# GPS_radiologger_v20_CAM_M8Q.net
KiCad netlist of a schematic drawn in EAGLE
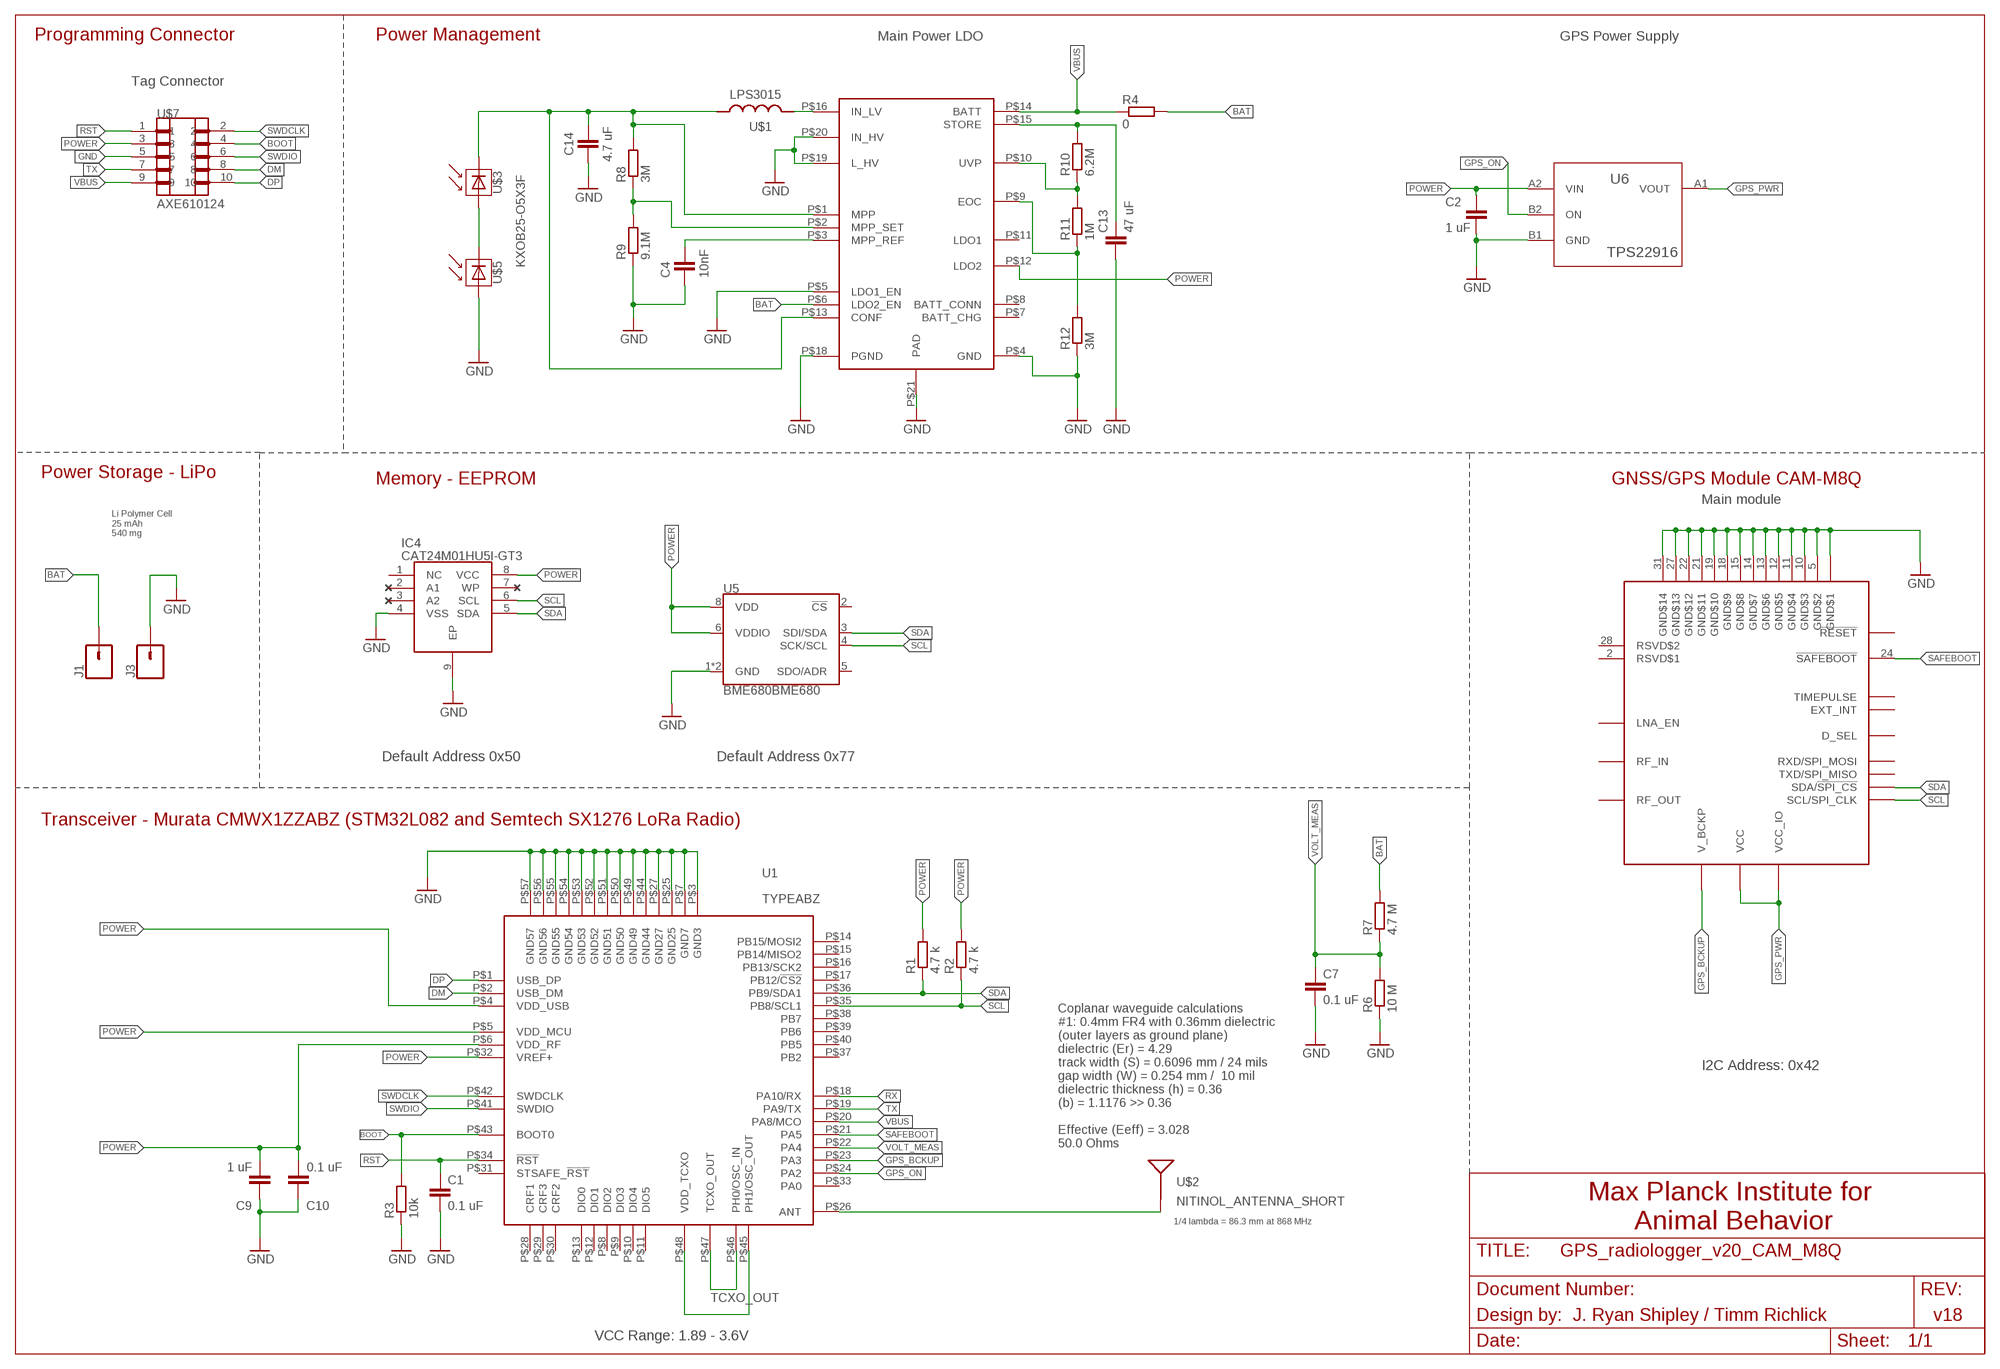
[diagram p0: schematic, sheet 1]

(export (version "E")
  (design (tool "Eeschema 10.0.6"))
  (components
    (comp (ref "C1")
      (value "0.1 uF")
      (footprint "eagle-import:C0201")
      (libsource (lib "eagle-import") (part "C-EUC0201"))
    )
    (comp (ref "C2")
      (value "1 uF")
      (footprint "eagle-import:C0201")
      (libsource (lib "eagle-import") (part "C-EUC0201"))
    )
    (comp (ref "C4")
      (value "10nF")
      (footprint "eagle-import:C0201")
      (libsource (lib "eagle-import") (part "C-EUC0201"))
    )
    (comp (ref "C7")
      (value "0.1 uF")
      (footprint "eagle-import:C0201")
      (libsource (lib "eagle-import") (part "C-EUC0201"))
    )
    (comp (ref "C9")
      (value "1 uF")
      (footprint "eagle-import:C0201")
      (libsource (lib "eagle-import") (part "C-EUC0201"))
    )
    (comp (ref "C10")
      (value "0.1 uF")
      (footprint "eagle-import:C0201")
      (libsource (lib "eagle-import") (part "C-EUC0201"))
    )
    (comp (ref "C13")
      (value "47 uF")
      (footprint "eagle-import:C0805K")
      (libsource (lib "eagle-import") (part "C-EUC0805K"))
    )
    (comp (ref "C14")
      (value "4.7 uF")
      (footprint "eagle-import:C0201")
      (libsource (lib "eagle-import") (part "C-EUC0201"))
    )
    (comp (ref "IC4")
      (value "CAT24M01HU5I-GT3")
      (footprint "eagle-import:SON50P300X200X55-9N")
      (fields
        (field (name "MOUSER_PART_NUMBER") "863-CAT24M01HU5I-GT3")
        (field (name "RS_PART_NUMBER") "7814831P")
      )
      (libsource (lib "eagle-import") (part "CAT24M01HU5I-GT3"))
    )
    (comp (ref "J1")
      (value "CONN_01PTH_NO_SILK_YES_STOP")
      (footprint "eagle-import:1X01_NO_SILK")
      (libsource (lib "eagle-import") (part "CONN_01PTH_NO_SILK_YES_STOP"))
    )
    (comp (ref "J3")
      (value "CONN_01PTH_NO_SILK_YES_STOP")
      (footprint "eagle-import:1X01_NO_SILK")
      (libsource (lib "eagle-import") (part "CONN_01PTH_NO_SILK_YES_STOP"))
    )
    (comp (ref "R1")
      (value "4.7 k")
      (footprint "eagle-import:R0201")
      (libsource (lib "eagle-import") (part "R-EU_R0201"))
    )
    (comp (ref "R2")
      (value "4.7 k")
      (footprint "eagle-import:R0201")
      (libsource (lib "eagle-import") (part "R-EU_R0201"))
    )
    (comp (ref "R3")
      (value "10k")
      (footprint "eagle-import:R0201")
      (libsource (lib "eagle-import") (part "R-EU_R0201"))
    )
    (comp (ref "R4")
      (value "0")
      (footprint "eagle-import:R0201")
      (libsource (lib "eagle-import") (part "R-EU_R0201"))
    )
    (comp (ref "R6")
      (value "10 M")
      (footprint "eagle-import:R0201")
      (libsource (lib "eagle-import") (part "R-EU_R0201"))
    )
    (comp (ref "R7")
      (value "4.7 M")
      (footprint "eagle-import:R0201")
      (libsource (lib "eagle-import") (part "R-EU_R0201"))
    )
    (comp (ref "R8")
      (value "3M")
      (footprint "eagle-import:R0201")
      (libsource (lib "eagle-import") (part "R-EU_R0201"))
    )
    (comp (ref "R9")
      (value "9.1M")
      (footprint "eagle-import:R0201")
      (libsource (lib "eagle-import") (part "R-EU_R0201"))
    )
    (comp (ref "R10")
      (value "6.2M")
      (footprint "eagle-import:R0201")
      (libsource (lib "eagle-import") (part "R-EU_R0201"))
    )
    (comp (ref "R11")
      (value "1M")
      (footprint "eagle-import:R0201")
      (libsource (lib "eagle-import") (part "R-EU_R0201"))
    )
    (comp (ref "R12")
      (value "3M")
      (footprint "eagle-import:R0201")
      (libsource (lib "eagle-import") (part "R-EU_R0201"))
    )
    (comp (ref "U$1")
      (value "LPS3015")
      (footprint "eagle-import:LPS_3015")
      (libsource (lib "eagle-import") (part "LPS3015"))
    )
    (comp (ref "U$2")
      (value "NITINOL_ANTENNA_SHORT")
      (footprint "eagle-import:ICARUS_NITINOL_ANTENNA_SHORT")
      (libsource (lib "eagle-import") (part "NITINOL_ANTENNA_SHORT"))
    )
    (comp (ref "U$3")
      (value "KXOB25-O5X3F")
      (footprint "eagle-import:KXOB25-05X3F")
      (libsource (lib "eagle-import") (part "KXOB25-O5X3F"))
    )
    (comp (ref "U$4")
      (value "CAM-M8")
      (footprint "eagle-import:CAM-M8")
      (libsource (lib "eagle-import") (part "CAM-M8"))
    )
    (comp (ref "U$5")
      (value "KXOB25-O5X3F")
      (footprint "eagle-import:KXOB25-05X3F")
      (libsource (lib "eagle-import") (part "KXOB25-O5X3F"))
    )
    (comp (ref "U$7")
      (value "AXE610124")
      (footprint "eagle-import:AXE610124")
      (libsource (lib "eagle-import") (part "AXE610124"))
    )
    (comp (ref "U1")
      (value "TYPEABZ")
      (footprint "eagle-import:TYPEABZ")
      (libsource (lib "eagle-import") (part "TYPEABZ"))
    )
    (comp (ref "U4")
      (value "SPV1050")
      (footprint "eagle-import:SPV1050")
      (libsource (lib "eagle-import") (part "SPV1050"))
    )
    (comp (ref "U5")
      (value "BME680BME680")
      (footprint "eagle-import:LGA3.0X3.0")
      (libsource (lib "eagle-import") (part "BME680BME680"))
    )
    (comp (ref "U6")
      (value "TPS22916")
      (footprint "eagle-import:TPS22916")
      (fields (field (name "MF") "Texas Instruments") (field (name "MP") "LP5900TL-3.0"))
      (libsource (lib "eagle-import") (part "TPS22916"))
    )
  )
  (nets
    (net (code "1") (name "/TCXO_OUT") (class "Default")
      (node (ref "U1") (pin "P$46") (pinfunction "PH0/OSC_IN_P$46") (pintype "bidirectional"))
      (node (ref "U1") (pin "P$47") (pinfunction "TCXO_OUT_P$47") (pintype "bidirectional"))
    )
    (net (code "2") (name "BAT") (class "Default")
      (node (ref "J1") (pin "1") (pinfunction "1_1") (pintype "passive"))
      (node (ref "R4") (pin "2") (pinfunction "2_2") (pintype "passive"))
      (node (ref "R7") (pin "2") (pinfunction "2_2") (pintype "passive"))
      (node (ref "U4") (pin "P$6") (pinfunction "LDO2_EN_P$6") (pintype "input"))
    )
    (net (code "3") (name "BOOT") (class "Default")
      (node (ref "R3") (pin "2") (pinfunction "2_2") (pintype "passive"))
      (node (ref "U$7") (pin "4") (pinfunction "4_4") (pintype "passive"))
      (node (ref "U1") (pin "P$43") (pinfunction "BOOT0_P$43") (pintype "bidirectional"))
    )
    (net (code "4") (name "DM") (class "Default")
      (node (ref "U$7") (pin "8") (pinfunction "8_8") (pintype "passive"))
      (node (ref "U1") (pin "P$2") (pinfunction "USB_DM_P$2") (pintype "bidirectional"))
    )
    (net (code "5") (name "DP") (class "Default")
      (node (ref "U$7") (pin "10") (pinfunction "10_10") (pintype "passive"))
      (node (ref "U1") (pin "P$1") (pinfunction "USB_DP_P$1") (pintype "bidirectional"))
    )
    (net (code "6") (name "GND") (class "Default")
      (node (ref "C1") (pin "2") (pinfunction "2_2") (pintype "passive"))
      (node (ref "C10") (pin "1") (pinfunction "1_1") (pintype "passive"))
      (node (ref "C13") (pin "2") (pinfunction "2_2") (pintype "passive"))
      (node (ref "C14") (pin "2") (pinfunction "2_2") (pintype "passive"))
      (node (ref "C2") (pin "2") (pinfunction "2_2") (pintype "passive"))
      (node (ref "C4") (pin "2") (pinfunction "2_2") (pintype "passive"))
      (node (ref "C7") (pin "2") (pinfunction "2_2") (pintype "passive"))
      (node (ref "C9") (pin "1") (pinfunction "1_1") (pintype "passive"))
      (node (ref "IC4") (pin "4") (pinfunction "VSS_4") (pintype "power_in"))
      (node (ref "IC4") (pin "9") (pinfunction "EP_9") (pintype "bidirectional"))
      (node (ref "J3") (pin "1") (pinfunction "1_1") (pintype "passive"))
      (node (ref "R12") (pin "1") (pinfunction "1_1") (pintype "passive"))
      (node (ref "R3") (pin "1") (pinfunction "1_1") (pintype "passive"))
      (node (ref "R6") (pin "1") (pinfunction "1_1") (pintype "passive"))
      (node (ref "R9") (pin "1") (pinfunction "1_1") (pintype "passive"))
      (node (ref "U$4") (pin "10") (pinfunction "GND$3_10") (pintype "power_in"))
      (node (ref "U$4") (pin "11") (pinfunction "GND$4_11") (pintype "power_in"))
      (node (ref "U$4") (pin "12") (pinfunction "GND$5_12") (pintype "power_in"))
      (node (ref "U$4") (pin "13") (pinfunction "GND$6_13") (pintype "power_in"))
      (node (ref "U$4") (pin "14") (pinfunction "GND$7_14") (pintype "power_in"))
      (node (ref "U$4") (pin "15") (pinfunction "GND$8_15") (pintype "power_in"))
      (node (ref "U$4") (pin "18") (pinfunction "GND$9_18") (pintype "power_in"))
      (node (ref "U$4") (pin "19") (pinfunction "GND$10_19") (pintype "power_in"))
      (node (ref "U$4") (pin "21") (pinfunction "GND$11_21") (pintype "power_in"))
      (node (ref "U$4") (pin "22") (pinfunction "GND$12_22") (pintype "power_in"))
      (node (ref "U$4") (pin "27") (pinfunction "GND$13_27") (pintype "power_in"))
      (node (ref "U$4") (pin "31") (pinfunction "GND$14_31") (pintype "power_in"))
      (node (ref "U$4") (pin "4") (pinfunction "GND$1_4") (pintype "power_in"))
      (node (ref "U$4") (pin "5") (pinfunction "GND$2_5") (pintype "power_in"))
      (node (ref "U$5") (pin "P$2") (pinfunction "MINUS_P$2") (pintype "passive"))
      (node (ref "U$7") (pin "5") (pinfunction "5_5") (pintype "passive"))
      (node (ref "U1") (pin "P$25") (pinfunction "GND25_P$25") (pintype "power_in"))
      (node (ref "U1") (pin "P$27") (pinfunction "GND27_P$27") (pintype "power_in"))
      (node (ref "U1") (pin "P$3") (pinfunction "GND3_P$3") (pintype "power_in"))
      (node (ref "U1") (pin "P$44") (pinfunction "GND44_P$44") (pintype "power_in"))
      (node (ref "U1") (pin "P$49") (pinfunction "GND49_P$49") (pintype "power_in"))
      (node (ref "U1") (pin "P$50") (pinfunction "GND50_P$50") (pintype "power_in"))
      (node (ref "U1") (pin "P$51") (pinfunction "GND51_P$51") (pintype "power_in"))
      (node (ref "U1") (pin "P$52") (pinfunction "GND52_P$52") (pintype "power_in"))
      (node (ref "U1") (pin "P$53") (pinfunction "GND53_P$53") (pintype "power_in"))
      (node (ref "U1") (pin "P$54") (pinfunction "GND54_P$54") (pintype "power_in"))
      (node (ref "U1") (pin "P$55") (pinfunction "GND55_P$55") (pintype "power_in"))
      (node (ref "U1") (pin "P$56") (pinfunction "GND56_P$56") (pintype "power_in"))
      (node (ref "U1") (pin "P$57") (pinfunction "GND57_P$57") (pintype "power_in"))
      (node (ref "U1") (pin "P$7") (pinfunction "GND7_P$7") (pintype "power_in"))
      (node (ref "U4") (pin "P$18") (pinfunction "PGND_P$18") (pintype "power_in"))
      (node (ref "U4") (pin "P$19") (pinfunction "L_HV_P$19") (pintype "power_in"))
      (node (ref "U4") (pin "P$20") (pinfunction "IN_HV_P$20") (pintype "power_in"))
      (node (ref "U4") (pin "P$21") (pinfunction "PAD_P$21") (pintype "power_in"))
      (node (ref "U4") (pin "P$4") (pinfunction "GND_P$4") (pintype "power_in"))
      (node (ref "U4") (pin "P$5") (pinfunction "LDO1_EN_P$5") (pintype "input"))
      (node (ref "U5") (pin "1") (pinfunction "GND_1") (pintype "bidirectional"))
      (node (ref "U5") (pin "7") (pinfunction "GND_7") (pintype "bidirectional"))
      (node (ref "U6") (pin "B1") (pinfunction "GND_B1") (pintype "passive"))
    )
    (net (code "7") (name "GPS_BCKUP") (class "Default")
      (node (ref "U$4") (pin "8") (pinfunction "V_BCKP_8") (pintype "power_in"))
      (node (ref "U1") (pin "P$23") (pinfunction "PA3_P$23") (pintype "bidirectional"))
    )
    (net (code "8") (name "GPS_ON") (class "Default")
      (node (ref "U1") (pin "P$24") (pinfunction "PA2_P$24") (pintype "bidirectional"))
      (node (ref "U6") (pin "B2") (pinfunction "ON_B2") (pintype "input"))
    )
    (net (code "9") (name "GPS_PWR") (class "Default")
      (node (ref "U$4") (pin "1") (pinfunction "VCC_IO_1") (pintype "power_in"))
      (node (ref "U$4") (pin "9") (pinfunction "VCC_9") (pintype "power_in"))
      (node (ref "U6") (pin "A1") (pinfunction "VOUT_A1") (pintype "output"))
    )
    (net (code "10") (name "Net-(U$1-1)") (class "Default")
      (node (ref "C14") (pin "1") (pinfunction "1_1") (pintype "passive"))
      (node (ref "R8") (pin "2") (pinfunction "2_2") (pintype "passive"))
      (node (ref "U$1") (pin "P$1") (pinfunction "1_P$1") (pintype "passive"))
      (node (ref "U$3") (pin "P$1") (pinfunction "PLUS_P$1") (pintype "passive"))
      (node (ref "U4") (pin "P$1") (pinfunction "MPP_P$1") (pintype "input"))
      (node (ref "U4") (pin "P$13") (pinfunction "CONF_P$13") (pintype "input"))
    )
    (net (code "11") (name "Net-(U$1-2)") (class "Default")
      (node (ref "U$1") (pin "P$2") (pinfunction "2_P$2") (pintype "passive"))
      (node (ref "U4") (pin "P$16") (pinfunction "IN_LV_P$16") (pintype "power_in"))
    )
    (net (code "12") (name "Net-(U$3-MINUS)") (class "Default")
      (node (ref "U$3") (pin "P$2") (pinfunction "MINUS_P$2") (pintype "passive"))
      (node (ref "U$5") (pin "P$1") (pinfunction "PLUS_P$1") (pintype "passive"))
    )
    (net (code "13") (name "Net-(U1-ANT)") (class "Default")
      (node (ref "U$2") (pin "1") (pinfunction "SIGNAL_1") (pintype "bidirectional"))
      (node (ref "U$2") (pin "2") (pinfunction "SIGNAL_2") (pintype "bidirectional"))
      (node (ref "U$2") (pin "3") (pinfunction "SIGNAL_3") (pintype "bidirectional"))
      (node (ref "U1") (pin "P$26") (pinfunction "ANT_P$26") (pintype "bidirectional"))
    )
    (net (code "14") (name "Net-(U1-PH1{slash}OSC_OUT)") (class "Default")
      (node (ref "U1") (pin "P$45") (pinfunction "PH1/OSC_OUT_P$45") (pintype "bidirectional"))
      (node (ref "U1") (pin "P$48") (pinfunction "VDD_TCXO_P$48") (pintype "power_in"))
    )
    (net (code "15") (name "Net-(U4-EOC)") (class "Default")
      (node (ref "R11") (pin "1") (pinfunction "1_1") (pintype "passive"))
      (node (ref "R12") (pin "2") (pinfunction "2_2") (pintype "passive"))
      (node (ref "U4") (pin "P$9") (pinfunction "EOC_P$9") (pintype "input"))
    )
    (net (code "16") (name "Net-(U4-MPP_REF)") (class "Default")
      (node (ref "C4") (pin "1") (pinfunction "1_1") (pintype "passive"))
      (node (ref "U4") (pin "P$3") (pinfunction "MPP_REF_P$3") (pintype "input"))
    )
    (net (code "17") (name "Net-(U4-MPP_SET)") (class "Default")
      (node (ref "R8") (pin "1") (pinfunction "1_1") (pintype "passive"))
      (node (ref "R9") (pin "2") (pinfunction "2_2") (pintype "passive"))
      (node (ref "U4") (pin "P$2") (pinfunction "MPP_SET_P$2") (pintype "input"))
    )
    (net (code "18") (name "Net-(U4-STORE)") (class "Default")
      (node (ref "C13") (pin "1") (pinfunction "1_1") (pintype "passive"))
      (node (ref "R10") (pin "2") (pinfunction "2_2") (pintype "passive"))
      (node (ref "U4") (pin "P$15") (pinfunction "STORE_P$15") (pintype "bidirectional"))
    )
    (net (code "19") (name "Net-(U4-UVP)") (class "Default")
      (node (ref "R10") (pin "1") (pinfunction "1_1") (pintype "passive"))
      (node (ref "R11") (pin "2") (pinfunction "2_2") (pintype "passive"))
      (node (ref "U4") (pin "P$10") (pinfunction "UVP_P$10") (pintype "input"))
    )
    (net (code "20") (name "POWER") (class "Default")
      (node (ref "C10") (pin "2") (pinfunction "2_2") (pintype "passive"))
      (node (ref "C2") (pin "1") (pinfunction "1_1") (pintype "passive"))
      (node (ref "C9") (pin "2") (pinfunction "2_2") (pintype "passive"))
      (node (ref "IC4") (pin "8") (pinfunction "VCC_8") (pintype "power_in"))
      (node (ref "R1") (pin "2") (pinfunction "2_2") (pintype "passive"))
      (node (ref "R2") (pin "2") (pinfunction "2_2") (pintype "passive"))
      (node (ref "U$7") (pin "3") (pinfunction "3_3") (pintype "passive"))
      (node (ref "U1") (pin "P$32") (pinfunction "VREF+_P$32") (pintype "power_in"))
      (node (ref "U1") (pin "P$4") (pinfunction "VDD_USB_P$4") (pintype "power_in"))
      (node (ref "U1") (pin "P$5") (pinfunction "VDD_MCU_P$5") (pintype "power_in"))
      (node (ref "U1") (pin "P$6") (pinfunction "VDD_RF_P$6") (pintype "power_in"))
      (node (ref "U4") (pin "P$12") (pinfunction "LDO2_P$12") (pintype "output"))
      (node (ref "U5") (pin "6") (pinfunction "VDDIO_6") (pintype "bidirectional"))
      (node (ref "U5") (pin "8") (pinfunction "VDD_8") (pintype "bidirectional"))
      (node (ref "U6") (pin "A2") (pinfunction "VIN_A2") (pintype "power_in"))
    )
    (net (code "21") (name "RST") (class "Default")
      (node (ref "C1") (pin "1") (pinfunction "1_1") (pintype "passive"))
      (node (ref "U$7") (pin "1") (pinfunction "1_1") (pintype "passive"))
      (node (ref "U1") (pin "P$34") (pinfunction "~{RST}_P$34") (pintype "bidirectional"))
    )
    (net (code "22") (name "RX") (class "Default")
      (node (ref "U1") (pin "P$18") (pinfunction "PA10/RX_P$18") (pintype "bidirectional"))
    )
    (net (code "23") (name "SAFEBOOT") (class "Default")
      (node (ref "U$4") (pin "24") (pinfunction "~{SAFEBOOT}_24") (pintype "input"))
      (node (ref "U1") (pin "P$21") (pinfunction "PA5_P$21") (pintype "bidirectional"))
    )
    (net (code "24") (name "SCL") (class "Default")
      (node (ref "IC4") (pin "6") (pinfunction "SCL_6") (pintype "bidirectional"))
      (node (ref "R2") (pin "1") (pinfunction "1_1") (pintype "passive"))
      (node (ref "U$4") (pin "6") (pinfunction "SCL/SPI_CLK_6") (pintype "input"))
      (node (ref "U1") (pin "P$35") (pinfunction "PB8/SCL1_P$35") (pintype "bidirectional"))
      (node (ref "U5") (pin "4") (pinfunction "SCK/SCL_4") (pintype "bidirectional"))
    )
    (net (code "25") (name "SDA") (class "Default")
      (node (ref "IC4") (pin "5") (pinfunction "SDA_5") (pintype "bidirectional"))
      (node (ref "R1") (pin "1") (pinfunction "1_1") (pintype "passive"))
      (node (ref "U$4") (pin "3") (pinfunction "SDA/~{SPI_CS}_3") (pintype "bidirectional"))
      (node (ref "U1") (pin "P$36") (pinfunction "PB9/SDA1_P$36") (pintype "bidirectional"))
      (node (ref "U5") (pin "3") (pinfunction "SDI/SDA_3") (pintype "bidirectional"))
    )
    (net (code "26") (name "SWDCLK") (class "Default")
      (node (ref "U$7") (pin "2") (pinfunction "2_2") (pintype "passive"))
      (node (ref "U1") (pin "P$42") (pinfunction "SWDCLK_P$42") (pintype "bidirectional"))
    )
    (net (code "27") (name "SWDIO") (class "Default")
      (node (ref "U$7") (pin "6") (pinfunction "6_6") (pintype "passive"))
      (node (ref "U1") (pin "P$41") (pinfunction "SWDIO_P$41") (pintype "bidirectional"))
    )
    (net (code "28") (name "TX") (class "Default")
      (node (ref "U$7") (pin "7") (pinfunction "7_7") (pintype "passive"))
      (node (ref "U1") (pin "P$19") (pinfunction "PA9/TX_P$19") (pintype "bidirectional"))
    )
    (net (code "29") (name "VBUS") (class "Default")
      (node (ref "R4") (pin "1") (pinfunction "1_1") (pintype "passive"))
      (node (ref "U$7") (pin "9") (pinfunction "9_9") (pintype "passive"))
      (node (ref "U1") (pin "P$20") (pinfunction "PA8/MCO_P$20") (pintype "bidirectional"))
      (node (ref "U4") (pin "P$14") (pinfunction "BATT_P$14") (pintype "bidirectional"))
    )
    (net (code "30") (name "VOLT_MEAS") (class "Default")
      (node (ref "C7") (pin "1") (pinfunction "1_1") (pintype "passive"))
      (node (ref "R6") (pin "2") (pinfunction "2_2") (pintype "passive"))
      (node (ref "R7") (pin "1") (pinfunction "1_1") (pintype "passive"))
      (node (ref "U1") (pin "P$22") (pinfunction "PA4_P$22") (pintype "bidirectional"))
    )
    (net (code "31") (name "unconnected-(IC4-A1-Pad2)") (class "Default")
      (node (ref "IC4") (pin "2") (pinfunction "A1_2") (pintype "bidirectional"))
    )
    (net (code "32") (name "unconnected-(IC4-A2-Pad3)") (class "Default")
      (node (ref "IC4") (pin "3") (pinfunction "A2_3") (pintype "bidirectional"))
    )
    (net (code "33") (name "unconnected-(IC4-NC-Pad1)") (class "Default")
      (node (ref "IC4") (pin "1") (pinfunction "NC_1") (pintype "no_connect"))
    )
    (net (code "34") (name "unconnected-(IC4-WP-Pad7)") (class "Default")
      (node (ref "IC4") (pin "7") (pinfunction "WP_7") (pintype "bidirectional"))
    )
    (net (code "35") (name "unconnected-(U$4-D_SEL-Pad20)") (class "Default")
      (node (ref "U$4") (pin "20") (pinfunction "D_SEL_20") (pintype "input"))
    )
    (net (code "36") (name "unconnected-(U$4-EXT_INT-Pad7)") (class "Default")
      (node (ref "U$4") (pin "7") (pinfunction "EXT_INT_7") (pintype "bidirectional"))
    )
    (net (code "37") (name "unconnected-(U$4-LNA_EN-Pad30)") (class "Default")
      (node (ref "U$4") (pin "30") (pinfunction "LNA_EN_30") (pintype "output"))
    )
    (net (code "38") (name "unconnected-(U$4-RF_IN-Pad17)") (class "Default")
      (node (ref "U$4") (pin "17") (pinfunction "RF_IN_17") (pintype "input"))
    )
    (net (code "39") (name "unconnected-(U$4-RF_OUT-Pad16)") (class "Default")
      (node (ref "U$4") (pin "16") (pinfunction "RF_OUT_16") (pintype "output"))
    )
    (net (code "40") (name "unconnected-(U$4-RSVD$1-Pad2)") (class "Default")
      (node (ref "U$4") (pin "2") (pinfunction "RSVD$1_2") (pintype "no_connect"))
    )
    (net (code "41") (name "unconnected-(U$4-RSVD$2-Pad28)") (class "Default")
      (node (ref "U$4") (pin "28") (pinfunction "RSVD$2_28") (pintype "no_connect"))
    )
    (net (code "42") (name "unconnected-(U$4-RXD{slash}SPI_MOSI-Pad26)") (class "Default")
      (node (ref "U$4") (pin "26") (pinfunction "RXD/SPI_MOSI_26") (pintype "input"))
    )
    (net (code "43") (name "unconnected-(U$4-TIMEPULSE-Pad29)") (class "Default")
      (node (ref "U$4") (pin "29") (pinfunction "TIMEPULSE_29") (pintype "output"))
    )
    (net (code "44") (name "unconnected-(U$4-TXD{slash}SPI_MISO-Pad25)") (class "Default")
      (node (ref "U$4") (pin "25") (pinfunction "TXD/SPI_MISO_25") (pintype "output"))
    )
    (net (code "45") (name "unconnected-(U$4-~{RESET}-Pad23)") (class "Default")
      (node (ref "U$4") (pin "23") (pinfunction "~{RESET}_23") (pintype "input"))
    )
    (net (code "46") (name "unconnected-(U1-CRF1-PadP$28)") (class "Default")
      (node (ref "U1") (pin "P$28") (pinfunction "CRF1_P$28") (pintype "no_connect"))
    )
    (net (code "47") (name "unconnected-(U1-CRF2-PadP$30)") (class "Default")
      (node (ref "U1") (pin "P$30") (pinfunction "CRF2_P$30") (pintype "no_connect"))
    )
    (net (code "48") (name "unconnected-(U1-CRF3-PadP$29)") (class "Default")
      (node (ref "U1") (pin "P$29") (pinfunction "CRF3_P$29") (pintype "no_connect"))
    )
    (net (code "49") (name "unconnected-(U1-DIO0-PadP$13)") (class "Default")
      (node (ref "U1") (pin "P$13") (pinfunction "DIO0_P$13") (pintype "no_connect"))
    )
    (net (code "50") (name "unconnected-(U1-DIO1-PadP$12)") (class "Default")
      (node (ref "U1") (pin "P$12") (pinfunction "DIO1_P$12") (pintype "no_connect"))
    )
    (net (code "51") (name "unconnected-(U1-DIO2-PadP$8)") (class "Default")
      (node (ref "U1") (pin "P$8") (pinfunction "DIO2_P$8") (pintype "no_connect"))
    )
    (net (code "52") (name "unconnected-(U1-DIO3-PadP$9)") (class "Default")
      (node (ref "U1") (pin "P$9") (pinfunction "DIO3_P$9") (pintype "no_connect"))
    )
    (net (code "53") (name "unconnected-(U1-DIO4-PadP$10)") (class "Default")
      (node (ref "U1") (pin "P$10") (pinfunction "DIO4_P$10") (pintype "bidirectional"))
    )
    (net (code "54") (name "unconnected-(U1-DIO5-PadP$11)") (class "Default")
      (node (ref "U1") (pin "P$11") (pinfunction "DIO5_P$11") (pintype "bidirectional"))
    )
    (net (code "55") (name "unconnected-(U1-PA0-PadP$33)") (class "Default")
      (node (ref "U1") (pin "P$33") (pinfunction "PA0_P$33") (pintype "bidirectional"))
    )
    (net (code "56") (name "unconnected-(U1-PB2-PadP$37)") (class "Default")
      (node (ref "U1") (pin "P$37") (pinfunction "PB2_P$37") (pintype "bidirectional"))
    )
    (net (code "57") (name "unconnected-(U1-PB5-PadP$40)") (class "Default")
      (node (ref "U1") (pin "P$40") (pinfunction "PB5_P$40") (pintype "bidirectional"))
    )
    (net (code "58") (name "unconnected-(U1-PB6-PadP$39)") (class "Default")
      (node (ref "U1") (pin "P$39") (pinfunction "PB6_P$39") (pintype "bidirectional"))
    )
    (net (code "59") (name "unconnected-(U1-PB7-PadP$38)") (class "Default")
      (node (ref "U1") (pin "P$38") (pinfunction "PB7_P$38") (pintype "bidirectional"))
    )
    (net (code "60") (name "unconnected-(U1-PB12{slash}~{CS2}-PadP$17)") (class "Default")
      (node (ref "U1") (pin "P$17") (pinfunction "PB12/~{CS2}_P$17") (pintype "bidirectional"))
    )
    (net (code "61") (name "unconnected-(U1-PB13{slash}SCK2-PadP$16)") (class "Default")
      (node (ref "U1") (pin "P$16") (pinfunction "PB13/SCK2_P$16") (pintype "bidirectional"))
    )
    (net (code "62") (name "unconnected-(U1-PB14{slash}MISO2-PadP$15)") (class "Default")
      (node (ref "U1") (pin "P$15") (pinfunction "PB14/MISO2_P$15") (pintype "bidirectional"))
    )
    (net (code "63") (name "unconnected-(U1-PB15{slash}MOSI2-PadP$14)") (class "Default")
      (node (ref "U1") (pin "P$14") (pinfunction "PB15/MOSI2_P$14") (pintype "bidirectional"))
    )
    (net (code "64") (name "unconnected-(U1-STSAFE_~{RST}-PadP$31)") (class "Default")
      (node (ref "U1") (pin "P$31") (pinfunction "STSAFE_~{RST}_P$31") (pintype "bidirectional"))
    )
    (net (code "65") (name "unconnected-(U4-BATT_CHG-PadP$7)") (class "Default")
      (node (ref "U4") (pin "P$7") (pinfunction "BATT_CHG_P$7") (pintype "open_collector"))
    )
    (net (code "66") (name "unconnected-(U4-BATT_CONN-PadP$8)") (class "Default")
      (node (ref "U4") (pin "P$8") (pinfunction "BATT_CONN_P$8") (pintype "open_collector"))
    )
    (net (code "67") (name "unconnected-(U4-LDO1-PadP$11)") (class "Default")
      (node (ref "U4") (pin "P$11") (pinfunction "LDO1_P$11") (pintype "output"))
    )
    (net (code "68") (name "unconnected-(U5-SDO{slash}ADR-Pad5)") (class "Default")
      (node (ref "U5") (pin "5") (pinfunction "SDO/ADR_5") (pintype "bidirectional"))
    )
    (net (code "69") (name "unconnected-(U5-~{CS}-Pad2)") (class "Default")
      (node (ref "U5") (pin "2") (pinfunction "~{CS}_2") (pintype "bidirectional"))
    )
  )
)
